# femtoBeacon_dongle_r2_0_1.net
KiCad netlist of a schematic drawn in EAGLE
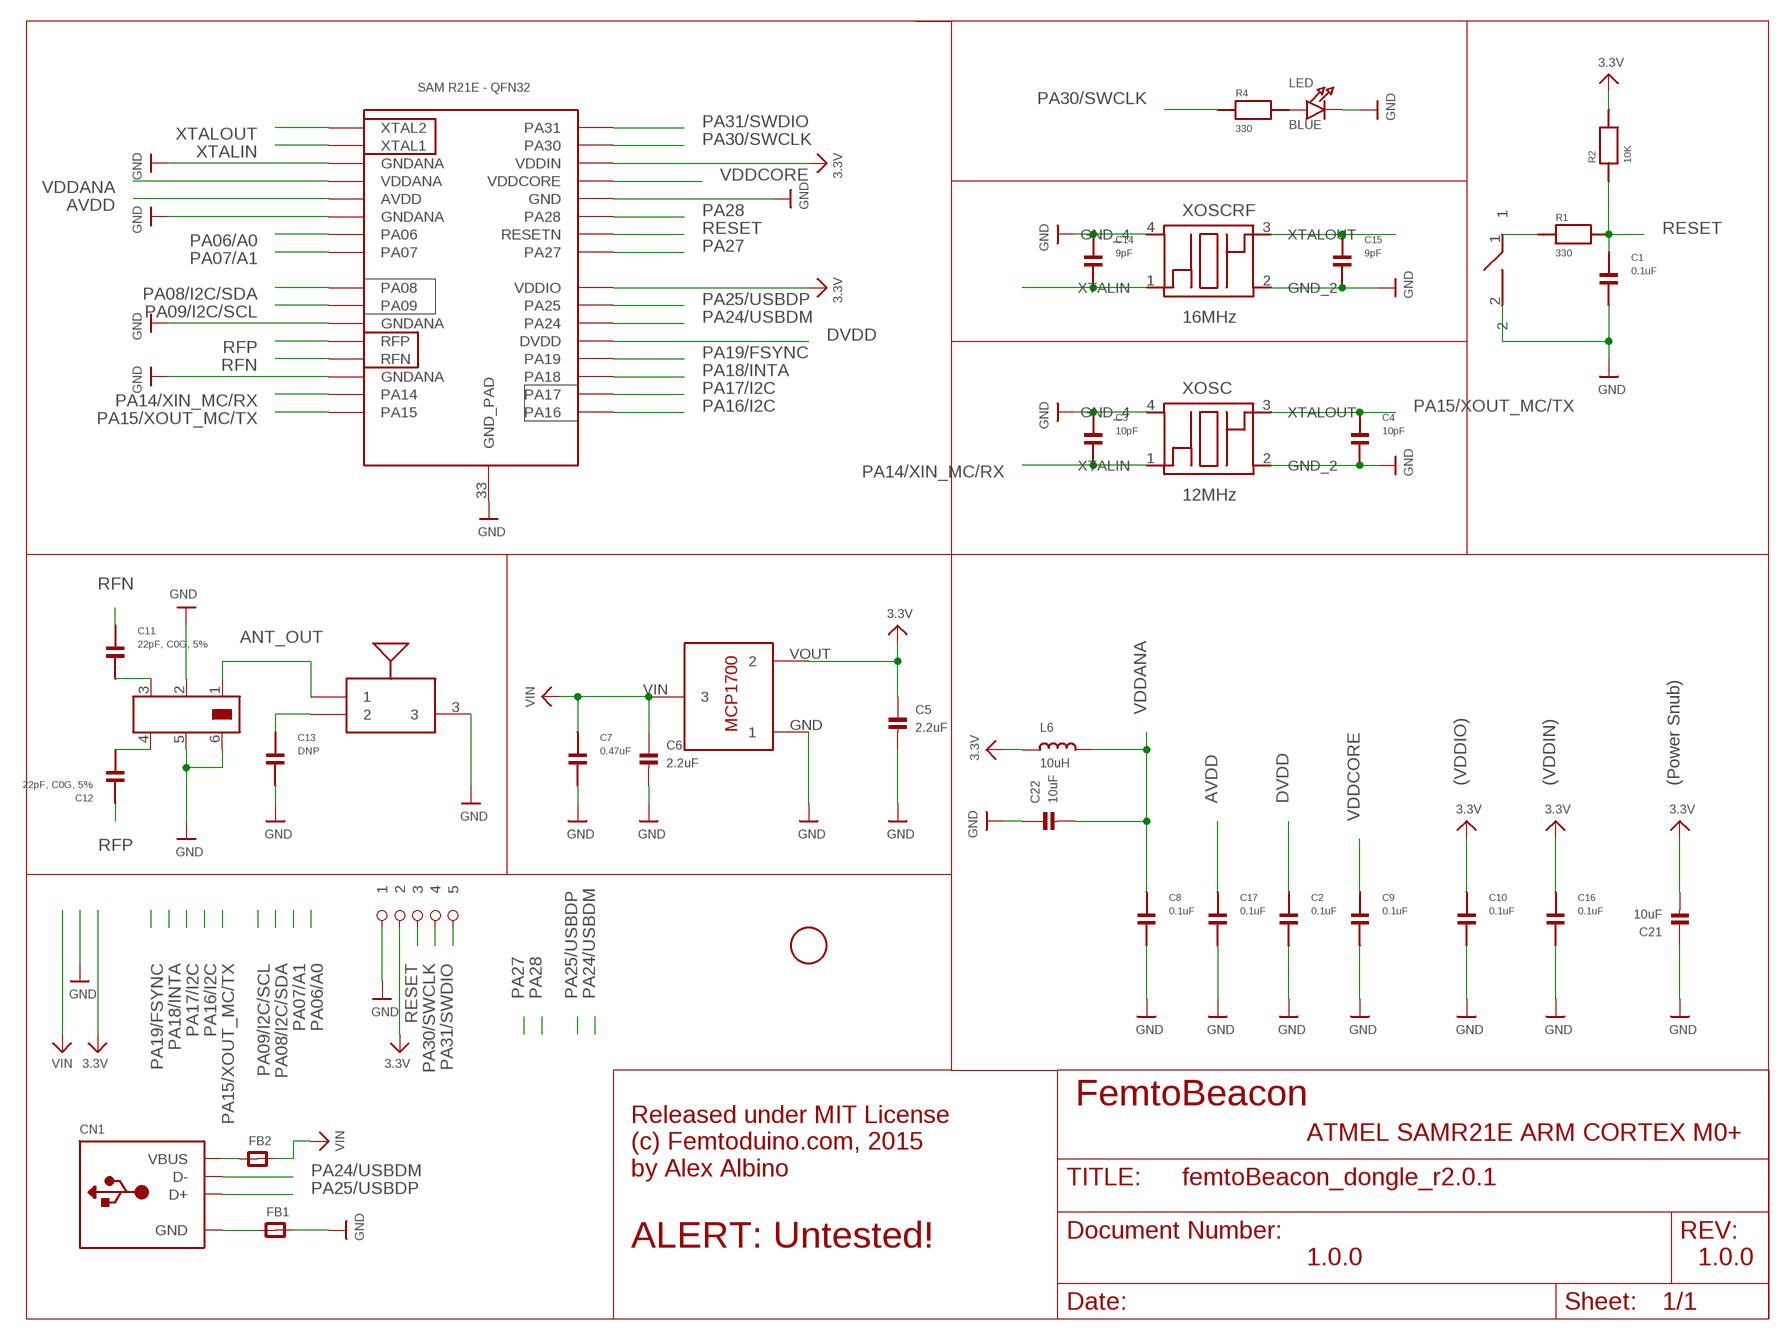
[diagram p0: schematic, sheet 1]

(export (version "E")
  (design (tool "Eeschema 10.0.6"))
  (components
    (comp (ref "ANT1")
      (value "PULSE_ANT_2.4GHZ")
      (footprint "eagle-import:ANT_BAR")
      (libsource (lib "eagle-import") (part "PULSE_ANT_2.4GHZ"))
    )
    (comp (ref "BTN")
      (value "DNP")
      (footprint "eagle-import:SPST_SMD")
      (libsource (lib "eagle-import") (part "SPST_SMD"))
    )
    (comp (ref "C1")
      (value "0.1uF")
      (footprint "eagle-import:PART")
      (fields (field (name "DIGIKEY_PART") "490-3194-1-ND"))
      (libsource (lib "eagle-import") (part "CAPACITOR_0201"))
    )
    (comp (ref "C2")
      (value "0.1uF")
      (footprint "eagle-import:PART")
      (libsource (lib "eagle-import") (part "CAPACITOR_0201"))
    )
    (comp (ref "C3")
      (value "10pF")
      (footprint "eagle-import:PART")
      (fields (field (name "DIGIKEY_PART") "490-3194-1-ND"))
      (libsource (lib "eagle-import") (part "CAPACITOR_0201"))
    )
    (comp (ref "C4")
      (value "10pF")
      (footprint "eagle-import:PART")
      (fields (field (name "DIGIKEY_PART") "490-3194-1-ND"))
      (libsource (lib "eagle-import") (part "CAPACITOR_0201"))
    )
    (comp (ref "C5")
      (value "2.2uF")
      (footprint "eagle-import:_0402MP")
      (libsource (lib "eagle-import") (part "CAP_CERAMIC_0402MP"))
    )
    (comp (ref "C6")
      (value "2.2uF")
      (footprint "eagle-import:_0402MP")
      (libsource (lib "eagle-import") (part "CAP_CERAMIC_0402MP"))
    )
    (comp (ref "C7")
      (value "0.47uF")
      (footprint "eagle-import:PART")
      (libsource (lib "eagle-import") (part "CAPACITOR_0201"))
    )
    (comp (ref "C8")
      (value "0.1uF")
      (footprint "eagle-import:PART")
      (fields (field (name "DIGIKEY_PART") "490-3194-1-ND"))
      (libsource (lib "eagle-import") (part "CAPACITOR_0201"))
    )
    (comp (ref "C9")
      (value "0.1uF")
      (footprint "eagle-import:PART")
      (fields (field (name "DIGIKEY_PART") "490-3194-1-ND"))
      (libsource (lib "eagle-import") (part "CAPACITOR_0201"))
    )
    (comp (ref "C10")
      (value "0.1uF")
      (footprint "eagle-import:PART")
      (fields (field (name "DIGIKEY_PART") "490-3194-1-ND"))
      (libsource (lib "eagle-import") (part "CAPACITOR_0201"))
    )
    (comp (ref "C11")
      (value "22pF, C0G, 5%")
      (footprint "eagle-import:PART")
      (fields (field (name "DIGIKEY_PART") "490-3194-1-ND"))
      (libsource (lib "eagle-import") (part "CAPACITOR_0201"))
    )
    (comp (ref "C12")
      (value "22pF, C0G, 5%")
      (footprint "eagle-import:PART")
      (fields (field (name "DIGIKEY_PART") "490-3194-1-ND"))
      (libsource (lib "eagle-import") (part "CAPACITOR_0201"))
    )
    (comp (ref "C13")
      (value "DNP")
      (footprint "eagle-import:PART")
      (fields (field (name "DIGIKEY_PART") "490-3194-1-ND"))
      (libsource (lib "eagle-import") (part "CAPACITOR_0201"))
    )
    (comp (ref "C14")
      (value "9pF")
      (footprint "eagle-import:PART")
      (fields (field (name "DIGIKEY_PART") "490-3194-1-ND"))
      (libsource (lib "eagle-import") (part "CAPACITOR_0201"))
    )
    (comp (ref "C15")
      (value "9pF")
      (footprint "eagle-import:PART")
      (fields (field (name "DIGIKEY_PART") "490-3194-1-ND"))
      (libsource (lib "eagle-import") (part "CAPACITOR_0201"))
    )
    (comp (ref "C16")
      (value "0.1uF")
      (footprint "eagle-import:PART")
      (fields (field (name "DIGIKEY_PART") "490-3194-1-ND"))
      (libsource (lib "eagle-import") (part "CAPACITOR_0201"))
    )
    (comp (ref "C17")
      (value "0.1uF")
      (footprint "eagle-import:PART")
      (fields (field (name "DIGIKEY_PART") "490-3194-1-ND"))
      (libsource (lib "eagle-import") (part "CAPACITOR_0201"))
    )
    (comp (ref "C21")
      (value "10uF")
      (footprint "eagle-import:_0402MP")
      (libsource (lib "eagle-import") (part "CAP_CERAMIC_0402MP"))
    )
    (comp (ref "C22")
      (value "10uF")
      (footprint "eagle-import:_0402MP")
      (libsource (lib "eagle-import") (part "CAP_CERAMIC_0402MP"))
    )
    (comp (ref "CN1")
      (value "USB_TYPEA")
      (footprint "eagle-import:USB_A-SMT")
      (libsource (lib "eagle-import") (part "USB_TYPEA"))
    )
    (comp (ref "FB1")
      (value "FERRITE_0603MP")
      (footprint "eagle-import:_0603MP")
      (libsource (lib "eagle-import") (part "FERRITE_0603MP"))
    )
    (comp (ref "FB2")
      (value "FERRITE_0603MP")
      (footprint "eagle-import:_0603MP")
      (libsource (lib "eagle-import") (part "FERRITE_0603MP"))
    )
    (comp (ref "FIDUCIAL")
      (value "FIDUCIAL")
      (footprint "eagle-import:FIDUCIAL_1MM")
      (libsource (lib "eagle-import") (part "FIDUCIAL"))
    )
    (comp (ref "L6")
      (value "10uH")
      (footprint "eagle-import:_0603MP")
      (libsource (lib "eagle-import") (part "INDUCTOR_0603MP"))
    )
    (comp (ref "LDO_VREG")
      (value "MCP1700T-3302E/TT")
      (footprint "eagle-import:MCP1700T-3302E_TT")
      (libsource (lib "eagle-import") (part "MCP1700T-3302E/TT"))
    )
    (comp (ref "LED")
      (value "BLUE")
      (footprint "eagle-import:CHIPLED_0603_NOOUTLINE")
      (libsource (lib "eagle-import") (part "LED0603_NOOUTLINE"))
    )
    (comp (ref "R1")
      (value "330")
      (footprint "eagle-import:PART")
      (libsource (lib "eagle-import") (part "RESISTOR_0201"))
    )
    (comp (ref "R2")
      (value "10K")
      (footprint "eagle-import:PART")
      (libsource (lib "eagle-import") (part "RESISTOR_0201"))
    )
    (comp (ref "R4")
      (value "330")
      (footprint "eagle-import:PART")
      (libsource (lib "eagle-import") (part "RESISTOR_0201"))
    )
    (comp (ref "U$1")
      (value "1X5_ROUND")
      (footprint "eagle-import:1X5_ROUND")
      (libsource (lib "eagle-import") (part "1X5_ROUND"))
    )
    (comp (ref "U$12")
      (value "JOHANSON_2450BM15A0015E")
      (footprint "eagle-import:0805_BALUN")
      (libsource (lib "eagle-import") (part "JOHANSON_2450BM15A0015E"))
    )
    (comp (ref "U$76")
      (value "ATSAMR21E18A-MUT")
      (footprint "eagle-import:QFN32")
      (libsource (lib "eagle-import") (part "ATSAMR21E18A-MUT"))
    )
    (comp (ref "XOSC")
      (value "12MHz")
      (footprint "eagle-import:TSX-3225")
      (libsource (lib "eagle-import") (part "TSX-3225"))
    )
    (comp (ref "XOSCRF")
      (value "16MHz")
      (footprint "eagle-import:TSX-3225")
      (libsource (lib "eagle-import") (part "TSX-3225"))
    )
  )
  (nets
    (net (code "1") (name "/ANT_OUT") (class "Default")
      (node (ref "ANT1") (pin "1") (pinfunction "1_1") (pintype "bidirectional"))
      (node (ref "U$12") (pin "1") (pinfunction "1_1") (pintype "bidirectional"))
    )
    (net (code "2") (name "/AVDD") (class "Default")
      (node (ref "C17") (pin "1") (pinfunction "P$1_1") (pintype "bidirectional"))
      (node (ref "U$76") (pin "5") (pinfunction "AVDD_5") (pintype "bidirectional"))
    )
    (net (code "3") (name "/DVDD") (class "Default")
      (node (ref "C2") (pin "1") (pinfunction "P$1_1") (pintype "bidirectional"))
      (node (ref "U$76") (pin "21") (pinfunction "DVDD_21") (pintype "bidirectional"))
    )
    (net (code "4") (name "/PA06{slash}A0") (class "Default")
      (node (ref "U$76") (pin "7") (pinfunction "PA06_7") (pintype "bidirectional"))
    )
    (net (code "5") (name "/PA07{slash}A1") (class "Default")
      (node (ref "U$76") (pin "8") (pinfunction "PA07_8") (pintype "bidirectional"))
    )
    (net (code "6") (name "/PA08{slash}I2C{slash}SDA") (class "Default")
      (node (ref "U$76") (pin "9") (pinfunction "PA08_9") (pintype "bidirectional"))
    )
    (net (code "7") (name "/PA09{slash}I2C{slash}SCL") (class "Default")
      (node (ref "U$76") (pin "10") (pinfunction "PA09_10") (pintype "bidirectional"))
    )
    (net (code "8") (name "/PA14{slash}XIN_MC{slash}RX") (class "Default")
      (node (ref "C3") (pin "2") (pinfunction "P$2_2") (pintype "bidirectional"))
      (node (ref "U$76") (pin "15") (pinfunction "PA14_15") (pintype "bidirectional"))
      (node (ref "XOSC") (pin "1") (pinfunction "XTALIN_1") (pintype "bidirectional"))
    )
    (net (code "9") (name "/PA15{slash}XOUT_MC{slash}TX") (class "Default")
      (node (ref "C4") (pin "1") (pinfunction "P$1_1") (pintype "bidirectional"))
      (node (ref "U$76") (pin "16") (pinfunction "PA15_16") (pintype "bidirectional"))
      (node (ref "XOSC") (pin "3") (pinfunction "XTALOUT_3") (pintype "bidirectional"))
    )
    (net (code "10") (name "/PA16{slash}I2C") (class "Default")
      (node (ref "U$76") (pin "17") (pinfunction "PA16_17") (pintype "bidirectional"))
    )
    (net (code "11") (name "/PA17{slash}I2C") (class "Default")
      (node (ref "U$76") (pin "18") (pinfunction "PA17_18") (pintype "bidirectional"))
    )
    (net (code "12") (name "/PA18{slash}INTA") (class "Default")
      (node (ref "U$76") (pin "19") (pinfunction "PA18_19") (pintype "bidirectional"))
    )
    (net (code "13") (name "/PA19{slash}FSYNC") (class "Default")
      (node (ref "U$76") (pin "20") (pinfunction "PA19_20") (pintype "bidirectional"))
    )
    (net (code "14") (name "/PA24{slash}USBDM") (class "Default")
      (node (ref "CN1") (pin "D-") (pinfunction "D-_D-") (pintype "bidirectional"))
      (node (ref "U$76") (pin "22") (pinfunction "PA24_22") (pintype "bidirectional"))
    )
    (net (code "15") (name "/PA25{slash}USBDP") (class "Default")
      (node (ref "CN1") (pin "D+") (pinfunction "D+_D+") (pintype "bidirectional"))
      (node (ref "U$76") (pin "23") (pinfunction "PA25_23") (pintype "bidirectional"))
    )
    (net (code "16") (name "/PA27") (class "Default")
      (node (ref "U$76") (pin "25") (pinfunction "PA27_25") (pintype "bidirectional"))
    )
    (net (code "17") (name "/PA28") (class "Default")
      (node (ref "U$76") (pin "27") (pinfunction "PA28_27") (pintype "bidirectional"))
    )
    (net (code "18") (name "/PA30{slash}SWCLK") (class "Default")
      (node (ref "R4") (pin "1") (pinfunction "1_1") (pintype "bidirectional"))
      (node (ref "U$1") (pin "P$4") (pinfunction "4_P$4") (pintype "bidirectional"))
      (node (ref "U$76") (pin "31") (pinfunction "PA30_31") (pintype "bidirectional"))
    )
    (net (code "19") (name "/PA31{slash}SWDIO") (class "Default")
      (node (ref "U$1") (pin "P$5") (pinfunction "5_P$5") (pintype "bidirectional"))
      (node (ref "U$76") (pin "32") (pinfunction "PA31_32") (pintype "bidirectional"))
    )
    (net (code "20") (name "/RESET") (class "Default")
      (node (ref "C1") (pin "1") (pinfunction "P$1_1") (pintype "bidirectional"))
      (node (ref "R1") (pin "2") (pinfunction "2_2") (pintype "bidirectional"))
      (node (ref "R2") (pin "1") (pinfunction "1_1") (pintype "bidirectional"))
      (node (ref "U$1") (pin "P$3") (pinfunction "3_P$3") (pintype "bidirectional"))
      (node (ref "U$76") (pin "26") (pinfunction "RESETN_26") (pintype "bidirectional"))
    )
    (net (code "21") (name "/RFN") (class "Default")
      (node (ref "C11") (pin "1") (pinfunction "P$1_1") (pintype "bidirectional"))
      (node (ref "U$76") (pin "13") (pinfunction "RFN_13") (pintype "bidirectional"))
    )
    (net (code "22") (name "/RFP") (class "Default")
      (node (ref "C12") (pin "1") (pinfunction "P$1_1") (pintype "bidirectional"))
      (node (ref "U$76") (pin "12") (pinfunction "RFP_12") (pintype "bidirectional"))
    )
    (net (code "23") (name "/VDDANA") (class "Default")
      (node (ref "C22") (pin "2") (pinfunction "P$2_2") (pintype "passive"))
      (node (ref "C8") (pin "1") (pinfunction "P$1_1") (pintype "bidirectional"))
      (node (ref "L6") (pin "2") (pinfunction "2_2") (pintype "passive"))
      (node (ref "U$76") (pin "4") (pinfunction "VDDANA_4") (pintype "bidirectional"))
    )
    (net (code "24") (name "/VDDCORE") (class "Default")
      (node (ref "C9") (pin "1") (pinfunction "P$1_1") (pintype "bidirectional"))
      (node (ref "U$76") (pin "29") (pinfunction "VDDCORE_29") (pintype "bidirectional"))
    )
    (net (code "25") (name "/XTALIN") (class "Default")
      (node (ref "C14") (pin "2") (pinfunction "P$2_2") (pintype "bidirectional"))
      (node (ref "U$76") (pin "2") (pinfunction "XTAL1_2") (pintype "bidirectional"))
      (node (ref "XOSCRF") (pin "1") (pinfunction "XTALIN_1") (pintype "bidirectional"))
    )
    (net (code "26") (name "/XTALOUT") (class "Default")
      (node (ref "C15") (pin "1") (pinfunction "P$1_1") (pintype "bidirectional"))
      (node (ref "U$76") (pin "1") (pinfunction "XTAL2_1") (pintype "bidirectional"))
      (node (ref "XOSCRF") (pin "3") (pinfunction "XTALOUT_3") (pintype "bidirectional"))
    )
    (net (code "27") (name "3.3V") (class "Default")
      (node (ref "C10") (pin "1") (pinfunction "P$1_1") (pintype "bidirectional"))
      (node (ref "C16") (pin "1") (pinfunction "P$1_1") (pintype "bidirectional"))
      (node (ref "C21") (pin "2") (pinfunction "P$2_2") (pintype "passive"))
      (node (ref "C5") (pin "1") (pinfunction "P$1_1") (pintype "passive"))
      (node (ref "L6") (pin "1") (pinfunction "1_1") (pintype "passive"))
      (node (ref "LDO_VREG") (pin "VOUT") (pinfunction "2_VOUT") (pintype "bidirectional"))
      (node (ref "R2") (pin "2") (pinfunction "2_2") (pintype "bidirectional"))
      (node (ref "U$1") (pin "P$2") (pinfunction "2_P$2") (pintype "bidirectional"))
      (node (ref "U$76") (pin "24") (pinfunction "VDDIO_24") (pintype "bidirectional"))
      (node (ref "U$76") (pin "30") (pinfunction "VDDIN_30") (pintype "bidirectional"))
    )
    (net (code "28") (name "GND") (class "Default")
      (node (ref "ANT1") (pin "3") (pinfunction "3_3") (pintype "bidirectional"))
      (node (ref "BTN") (pin "2") (pinfunction "2_2") (pintype "bidirectional"))
      (node (ref "C1") (pin "2") (pinfunction "P$2_2") (pintype "bidirectional"))
      (node (ref "C10") (pin "2") (pinfunction "P$2_2") (pintype "bidirectional"))
      (node (ref "C13") (pin "2") (pinfunction "P$2_2") (pintype "bidirectional"))
      (node (ref "C14") (pin "1") (pinfunction "P$1_1") (pintype "bidirectional"))
      (node (ref "C15") (pin "2") (pinfunction "P$2_2") (pintype "bidirectional"))
      (node (ref "C16") (pin "2") (pinfunction "P$2_2") (pintype "bidirectional"))
      (node (ref "C17") (pin "2") (pinfunction "P$2_2") (pintype "bidirectional"))
      (node (ref "C2") (pin "2") (pinfunction "P$2_2") (pintype "bidirectional"))
      (node (ref "C21") (pin "1") (pinfunction "P$1_1") (pintype "passive"))
      (node (ref "C22") (pin "1") (pinfunction "P$1_1") (pintype "passive"))
      (node (ref "C3") (pin "1") (pinfunction "P$1_1") (pintype "bidirectional"))
      (node (ref "C4") (pin "2") (pinfunction "P$2_2") (pintype "bidirectional"))
      (node (ref "C5") (pin "2") (pinfunction "P$2_2") (pintype "passive"))
      (node (ref "C6") (pin "2") (pinfunction "P$2_2") (pintype "passive"))
      (node (ref "C7") (pin "2") (pinfunction "P$2_2") (pintype "bidirectional"))
      (node (ref "C8") (pin "2") (pinfunction "P$2_2") (pintype "bidirectional"))
      (node (ref "C9") (pin "2") (pinfunction "P$2_2") (pintype "bidirectional"))
      (node (ref "FB1") (pin "2") (pinfunction "P$2_2") (pintype "passive"))
      (node (ref "LDO_VREG") (pin "GND") (pinfunction "1_GND") (pintype "bidirectional"))
      (node (ref "LED") (pin "C") (pinfunction "C_C") (pintype "passive"))
      (node (ref "U$1") (pin "P$1") (pinfunction "1_P$1") (pintype "bidirectional"))
      (node (ref "U$12") (pin "2") (pinfunction "2_2") (pintype "bidirectional"))
      (node (ref "U$12") (pin "5") (pinfunction "5_5") (pintype "bidirectional"))
      (node (ref "U$12") (pin "6") (pinfunction "6_6") (pintype "bidirectional"))
      (node (ref "U$76") (pin "11") (pinfunction "GNDANA_11") (pintype "bidirectional"))
      (node (ref "U$76") (pin "14") (pinfunction "GNDANA_14") (pintype "bidirectional"))
      (node (ref "U$76") (pin "28") (pinfunction "GND_28") (pintype "bidirectional"))
      (node (ref "U$76") (pin "3") (pinfunction "GNDANA_3") (pintype "bidirectional"))
      (node (ref "U$76") (pin "33") (pinfunction "GND_PAD_33") (pintype "bidirectional"))
      (node (ref "U$76") (pin "6") (pinfunction "GNDANA_6") (pintype "bidirectional"))
      (node (ref "XOSC") (pin "2") (pinfunction "GND_2_2") (pintype "bidirectional"))
      (node (ref "XOSC") (pin "4") (pinfunction "GND_4_4") (pintype "bidirectional"))
      (node (ref "XOSCRF") (pin "2") (pinfunction "GND_2_2") (pintype "bidirectional"))
      (node (ref "XOSCRF") (pin "4") (pinfunction "GND_4_4") (pintype "bidirectional"))
    )
    (net (code "29") (name "Net-(BTN-Pad1)") (class "Default")
      (node (ref "BTN") (pin "1") (pinfunction "1_1") (pintype "bidirectional"))
      (node (ref "R1") (pin "1") (pinfunction "1_1") (pintype "bidirectional"))
    )
    (net (code "30") (name "Net-(C11-P$2)") (class "Default")
      (node (ref "C11") (pin "2") (pinfunction "P$2_2") (pintype "bidirectional"))
      (node (ref "U$12") (pin "3") (pinfunction "3_3") (pintype "bidirectional"))
    )
    (net (code "31") (name "Net-(C12-P$2)") (class "Default")
      (node (ref "C12") (pin "2") (pinfunction "P$2_2") (pintype "bidirectional"))
      (node (ref "U$12") (pin "4") (pinfunction "4_4") (pintype "bidirectional"))
    )
    (net (code "32") (name "Net-(C13-P$1)") (class "Default")
      (node (ref "ANT1") (pin "2") (pinfunction "2_2") (pintype "bidirectional"))
      (node (ref "C13") (pin "1") (pinfunction "P$1_1") (pintype "bidirectional"))
    )
    (net (code "33") (name "Net-(FB1-P$1)") (class "Default")
      (node (ref "CN1") (pin "GND") (pinfunction "GND_GND") (pintype "power_in"))
      (node (ref "FB1") (pin "1") (pinfunction "P$1_1") (pintype "passive"))
    )
    (net (code "34") (name "Net-(FB2-P$1)") (class "Default")
      (node (ref "CN1") (pin "VBUS") (pinfunction "VBUS_VBUS") (pintype "power_in"))
      (node (ref "FB2") (pin "1") (pinfunction "P$1_1") (pintype "passive"))
    )
    (net (code "35") (name "Net-(LED-PadA)") (class "Default")
      (node (ref "LED") (pin "A") (pinfunction "A_A") (pintype "passive"))
      (node (ref "R4") (pin "2") (pinfunction "2_2") (pintype "bidirectional"))
    )
    (net (code "36") (name "VIN") (class "Default")
      (node (ref "C6") (pin "1") (pinfunction "P$1_1") (pintype "passive"))
      (node (ref "C7") (pin "1") (pinfunction "P$1_1") (pintype "bidirectional"))
      (node (ref "FB2") (pin "2") (pinfunction "P$2_2") (pintype "passive"))
      (node (ref "LDO_VREG") (pin "VIN") (pinfunction "3_VIN") (pintype "bidirectional"))
    )
  )
)
